# Top.net
KiCad netlist of a schematic drawn in Altium Designer
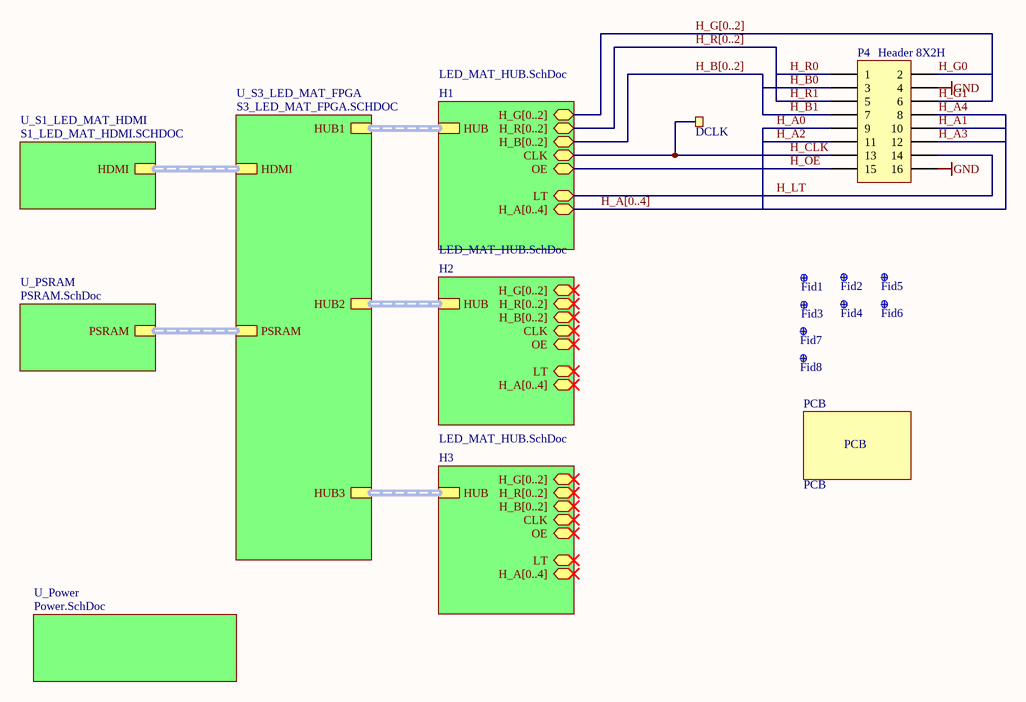
[diagram p0: Top.SchDoc]

(export (version "E")
  (design (tool "Eeschema 10.0.6"))
  (components
    (comp (ref "DCLK")
      (value "Ø1.0mm,SMD")
      (footprint "TP_SMD_1MM")
      (description "circular SMD testpad 1mm")
      (libsource (lib "LED_MAT_3") (part "TESTPAD_SMD"))
    )
    (comp (ref "Fid1")
      (value "Fiducial mark")
      (footprint "Pass-marke-02")
      (description "Fiducial Mark")
      (libsource (lib "LED_MAT_3") (part "Fiducial"))
    )
    (comp (ref "Fid2")
      (value "Fiducial mark")
      (footprint "Pass-marke-02")
      (description "Fiducial Mark")
      (libsource (lib "LED_MAT_3") (part "Fiducial"))
    )
    (comp (ref "Fid3")
      (value "Fiducial mark")
      (footprint "Pass-marke-02")
      (description "Fiducial Mark")
      (libsource (lib "LED_MAT_3") (part "Fiducial"))
    )
    (comp (ref "Fid4")
      (value "Fiducial mark")
      (footprint "Pass-marke-02")
      (description "Fiducial Mark")
      (libsource (lib "LED_MAT_3") (part "Fiducial"))
    )
    (comp (ref "Fid5")
      (value "Fiducial mark")
      (footprint "Pass-marke-02")
      (description "Fiducial Mark")
      (libsource (lib "LED_MAT_3") (part "Fiducial"))
    )
    (comp (ref "Fid6")
      (value "Fiducial mark")
      (footprint "Pass-marke-02")
      (description "Fiducial Mark")
      (libsource (lib "LED_MAT_3") (part "Fiducial"))
    )
    (comp (ref "Fid7")
      (value "Fiducial mark")
      (footprint "Pass-marke-02")
      (description "Fiducial Mark")
      (libsource (lib "LED_MAT_3") (part "Fiducial"))
    )
    (comp (ref "Fid8")
      (value "Fiducial mark")
      (footprint "Pass-marke-02")
      (description "Fiducial Mark")
      (libsource (lib "LED_MAT_3") (part "Fiducial"))
    )
    (comp (ref "P4")
      (value "Header 8X2H")
      (footprint "HDR2X8H")
      (description "Header, 8-Pin, Dual row, Right Angle")
      (libsource (lib "LED_MAT_3") (part "Header 8X2H"))
    )
    (comp (ref "PCB")
      (value "PCB")
      (description "PNEC_Bridge_v1 PCB/FR4/1.55mm/8L/ENIG")
      (fields (field (name "MANUFACTURER") "./."))
      (libsource (lib "DN_LIB-old") (part "PCB"))
    )
  )
  (nets
    (net (code "10") (name "/H_A0") (class "Default")
      (node (ref "P4") (pin "9") (pinfunction "9_9") (pintype "passive"))
    )
    (net (code "11") (name "/H_A1") (class "Default")
      (node (ref "P4") (pin "10") (pinfunction "10_10") (pintype "passive"))
    )
    (net (code "12") (name "/H_A2") (class "Default")
      (node (ref "P4") (pin "11") (pinfunction "11_11") (pintype "passive"))
    )
    (net (code "13") (name "/H_A3") (class "Default")
      (node (ref "P4") (pin "12") (pinfunction "12_12") (pintype "passive"))
    )
    (net (code "14") (name "/H_A4") (class "Default")
      (node (ref "P4") (pin "8") (pinfunction "8_8") (pintype "passive"))
    )
    (net (code "18") (name "/H_B0") (class "Default")
      (node (ref "P4") (pin "3") (pinfunction "3_3") (pintype "passive"))
    )
    (net (code "19") (name "/H_B1") (class "Default")
      (node (ref "P4") (pin "7") (pinfunction "7_7") (pintype "passive"))
    )
    (net (code "23") (name "/H_CLK") (class "Default")
      (node (ref "DCLK") (pin "1") (pinfunction "1_1") (pintype "passive"))
      (node (ref "P4") (pin "13") (pinfunction "13_13") (pintype "passive"))
    )
    (net (code "24") (name "/H_G0") (class "Default")
      (node (ref "P4") (pin "2") (pinfunction "2_2") (pintype "passive"))
    )
    (net (code "25") (name "/H_G1") (class "Default")
      (node (ref "P4") (pin "6") (pinfunction "6_6") (pintype "passive"))
    )
    (net (code "29") (name "/H_LT") (class "Default")
      (node (ref "P4") (pin "14") (pinfunction "14_14") (pintype "passive"))
    )
    (net (code "30") (name "/H_OE") (class "Default")
      (node (ref "P4") (pin "15") (pinfunction "15_15") (pintype "passive"))
    )
    (net (code "31") (name "/H_R0") (class "Default")
      (node (ref "P4") (pin "1") (pinfunction "1_1") (pintype "passive"))
    )
    (net (code "32") (name "/H_R1") (class "Default")
      (node (ref "P4") (pin "5") (pinfunction "5_5") (pintype "passive"))
    )
    (net (code "41") (name "GND") (class "Default")
      (node (ref "P4") (pin "16") (pinfunction "16_16") (pintype "passive"))
      (node (ref "P4") (pin "4") (pinfunction "4_4") (pintype "passive"))
    )
  )
)
